# adaptador_mcp3002_fpga.net
KiCad netlist of a schematic drawn in EAGLE
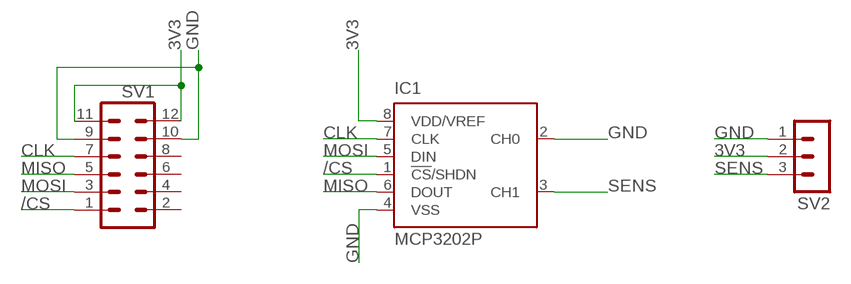
[diagram p0: schematic, sheet 1]

(export (version "E")
  (design (tool "Eeschema 10.0.6"))
  (components
    (comp (ref "IC1")
      (value "MCP3202P")
      (footprint "eagle-import:DIL8")
      (fields (field (name "MF") "MICROCHIP") (field (name "MPN") "MCP3202-CI/P"))
      (libsource (lib "eagle-import") (part "MCP3202P"))
    )
    (comp (ref "SV1")
      (value "MA06-2")
      (footprint "eagle-import:MA06-2")
      (libsource (lib "eagle-import") (part "MA06-2"))
    )
    (comp (ref "SV2")
      (value "MA03-1")
      (footprint "eagle-import:MA03-1")
      (libsource (lib "eagle-import") (part "MA03-1"))
    )
  )
  (nets
    (net (code "1") (name "/3V3") (class "Default")
      (node (ref "IC1") (pin "8") (pinfunction "VDD/VREF_8") (pintype "input"))
      (node (ref "SV1") (pin "11") (pinfunction "11_11") (pintype "passive"))
      (node (ref "SV1") (pin "12") (pinfunction "12_12") (pintype "passive"))
      (node (ref "SV2") (pin "2") (pinfunction "2_2") (pintype "passive"))
    )
    (net (code "2") (name "/CLK") (class "Default")
      (node (ref "IC1") (pin "7") (pinfunction "CLK_7") (pintype "input"))
      (node (ref "SV1") (pin "7") (pinfunction "7_7") (pintype "passive"))
    )
    (net (code "3") (name "/GND") (class "Default")
      (node (ref "IC1") (pin "2") (pinfunction "CH0_2") (pintype "input"))
      (node (ref "IC1") (pin "4") (pinfunction "VSS_4") (pintype "input"))
      (node (ref "SV1") (pin "10") (pinfunction "10_10") (pintype "passive"))
      (node (ref "SV1") (pin "9") (pinfunction "9_9") (pintype "passive"))
      (node (ref "SV2") (pin "1") (pinfunction "1_1") (pintype "passive"))
    )
    (net (code "4") (name "/MISO") (class "Default")
      (node (ref "IC1") (pin "6") (pinfunction "DOUT_6") (pintype "input"))
      (node (ref "SV1") (pin "5") (pinfunction "5_5") (pintype "passive"))
    )
    (net (code "5") (name "/MOSI") (class "Default")
      (node (ref "IC1") (pin "5") (pinfunction "DIN_5") (pintype "input"))
      (node (ref "SV1") (pin "3") (pinfunction "3_3") (pintype "passive"))
    )
    (net (code "6") (name "/SENS") (class "Default")
      (node (ref "IC1") (pin "3") (pinfunction "CH1_3") (pintype "input"))
      (node (ref "SV2") (pin "3") (pinfunction "3_3") (pintype "passive"))
    )
    (net (code "7") (name "/{slash}CS") (class "Default")
      (node (ref "IC1") (pin "1") (pinfunction "~{CS}/SHDN_1") (pintype "input"))
      (node (ref "SV1") (pin "1") (pinfunction "1_1") (pintype "passive"))
    )
    (net (code "8") (name "unconnected-(SV1-Pad2)") (class "Default")
      (node (ref "SV1") (pin "2") (pinfunction "2_2") (pintype "passive"))
    )
    (net (code "9") (name "unconnected-(SV1-Pad4)") (class "Default")
      (node (ref "SV1") (pin "4") (pinfunction "4_4") (pintype "passive"))
    )
    (net (code "10") (name "unconnected-(SV1-Pad6)") (class "Default")
      (node (ref "SV1") (pin "6") (pinfunction "6_6") (pintype "passive"))
    )
    (net (code "11") (name "unconnected-(SV1-Pad8)") (class "Default")
      (node (ref "SV1") (pin "8") (pinfunction "8_8") (pintype "passive"))
    )
  )
)
